# ADAPTER_WOLF.net
KiCad netlist of a schematic drawn in Altium Designer
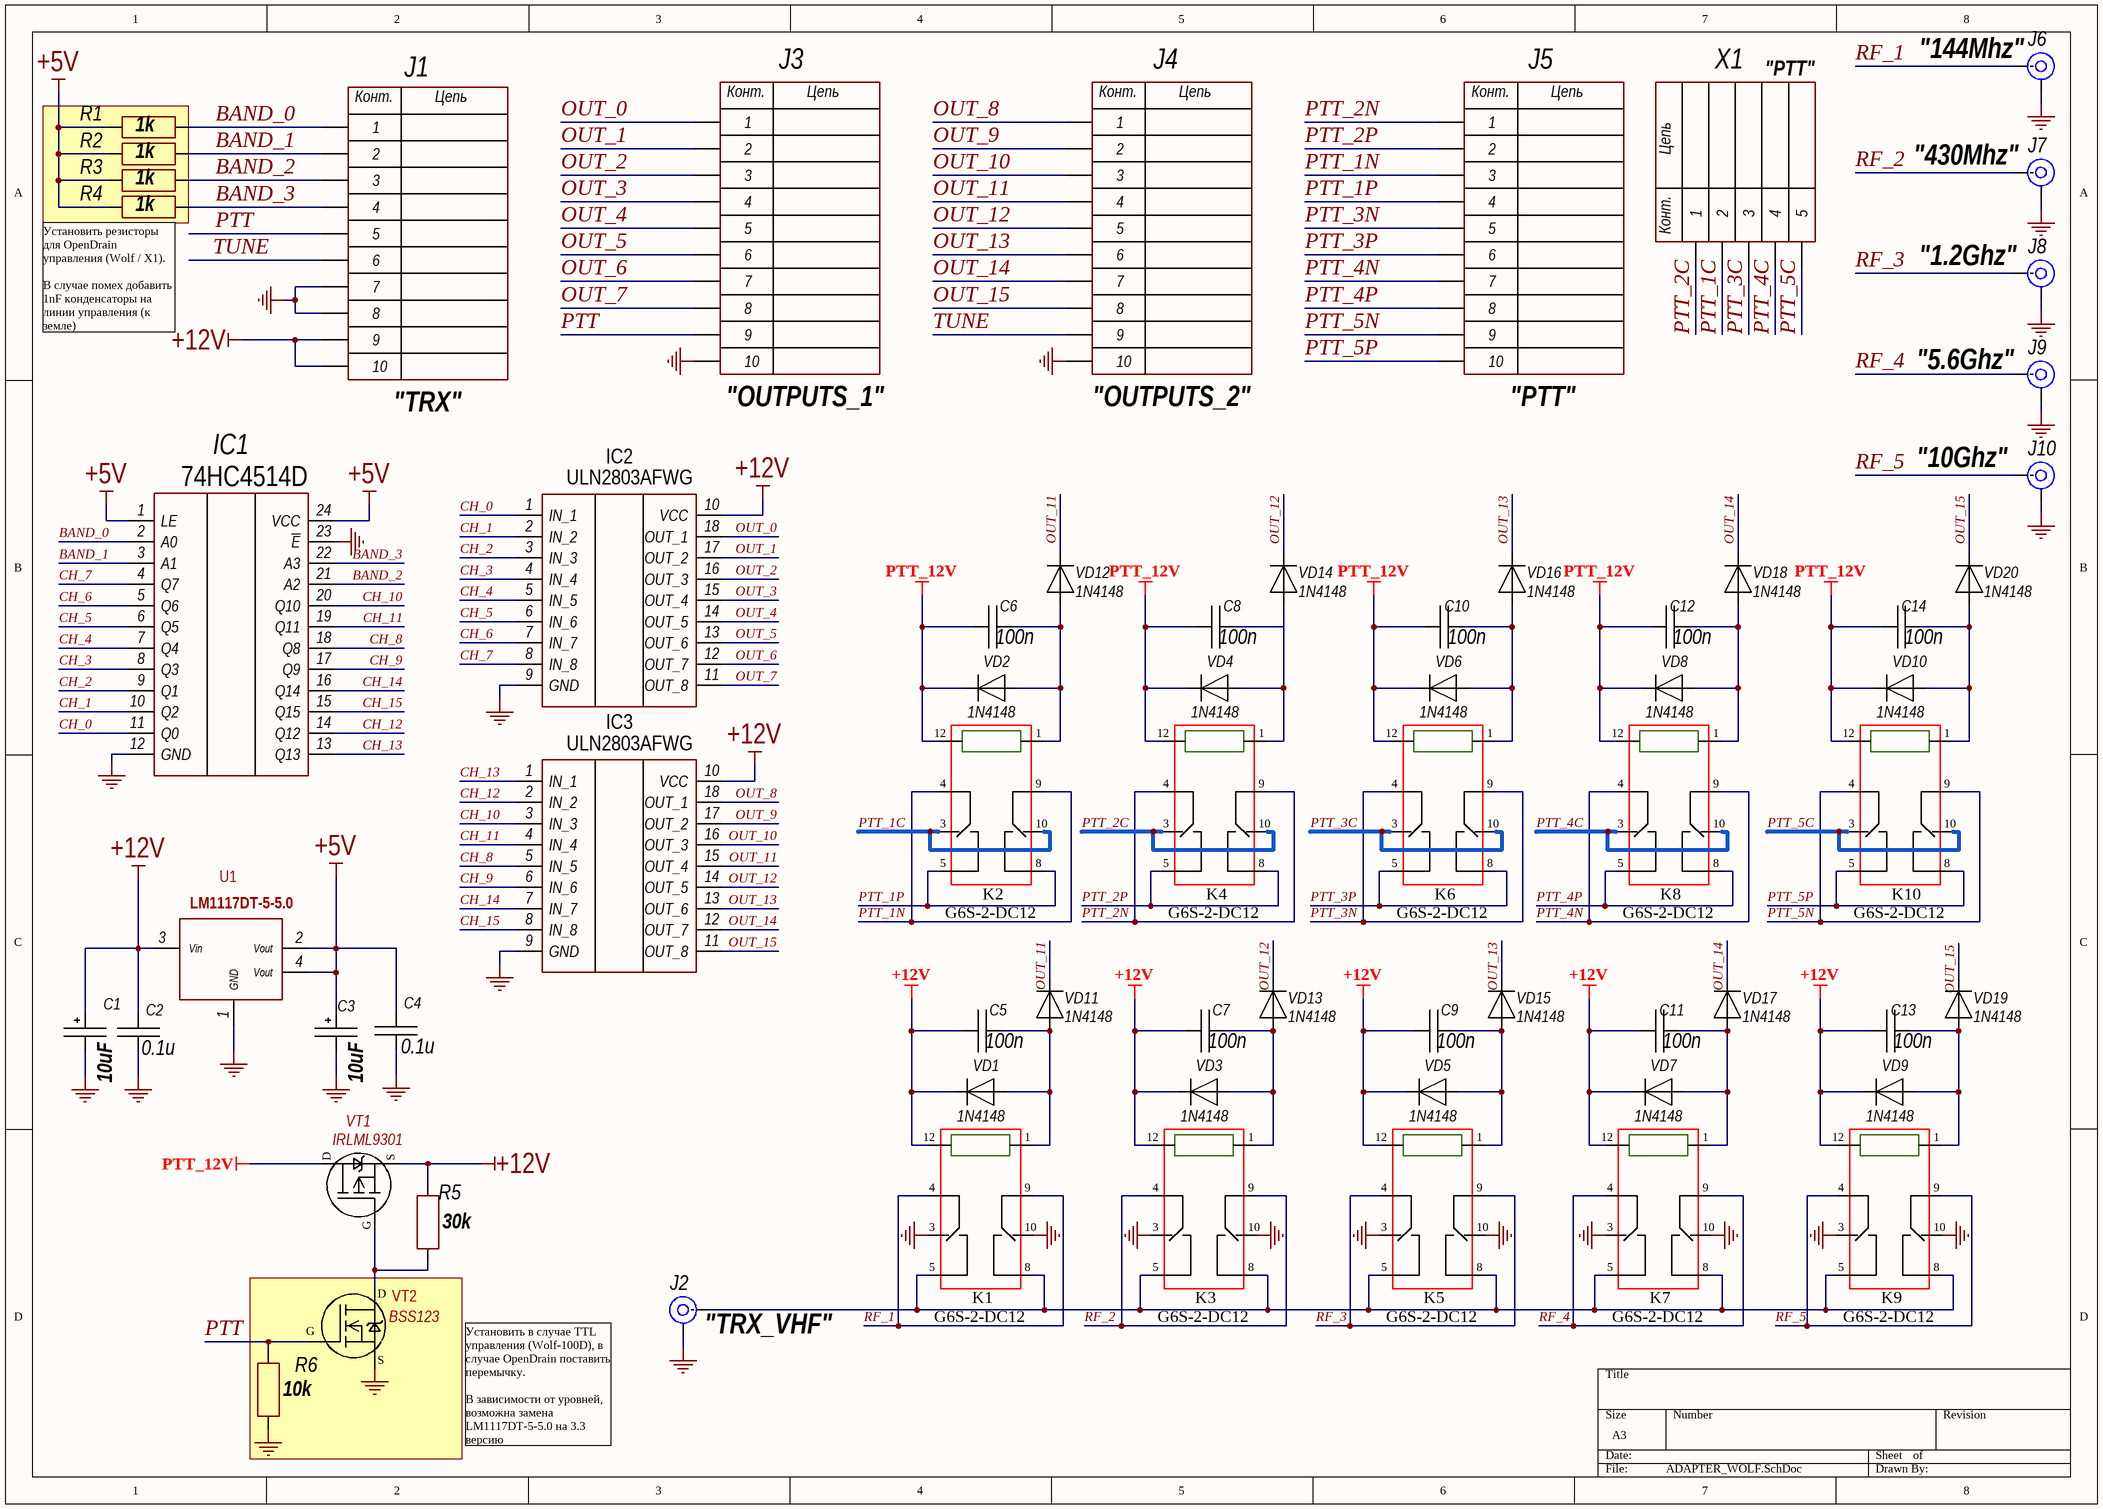
[diagram p0: ADAPTER_WOLF.SchDoc]

(export (version "E")
  (design (tool "Eeschema 10.0.6"))
  (components
    (comp (ref "C1")
      (value "10uF")
      (footprint "standard:TANTAL_B")
      (libsource (lib "Discrete") (part "TantalCap"))
    )
    (comp (ref "C2")
      (value "0.1u")
      (footprint "standard:CH0805C")
      (libsource (lib "Discrete") (part "Capacitor"))
    )
    (comp (ref "C3")
      (value "10uF")
      (footprint "standard:TANTAL_B")
      (libsource (lib "Discrete") (part "TantalCap"))
    )
    (comp (ref "C4")
      (value "0.1u")
      (footprint "standard:CH0805C")
      (libsource (lib "Discrete") (part "Capacitor"))
    )
    (comp (ref "C5")
      (value "100n")
      (footprint "standard:CH0805C")
      (libsource (lib "Discrete") (part "Capacitor"))
    )
    (comp (ref "C6")
      (value "100n")
      (footprint "standard:CH0805C")
      (libsource (lib "Discrete") (part "Capacitor"))
    )
    (comp (ref "C7")
      (value "100n")
      (footprint "standard:CH0805C")
      (libsource (lib "Discrete") (part "Capacitor"))
    )
    (comp (ref "C8")
      (value "100n")
      (footprint "standard:CH0805C")
      (libsource (lib "Discrete") (part "Capacitor"))
    )
    (comp (ref "C9")
      (value "100n")
      (footprint "standard:CH0805C")
      (libsource (lib "Discrete") (part "Capacitor"))
    )
    (comp (ref "C10")
      (value "100n")
      (footprint "standard:CH0805C")
      (libsource (lib "Discrete") (part "Capacitor"))
    )
    (comp (ref "C11")
      (value "100n")
      (footprint "standard:CH0805C")
      (libsource (lib "Discrete") (part "Capacitor"))
    )
    (comp (ref "C12")
      (value "100n")
      (footprint "standard:CH0805C")
      (libsource (lib "Discrete") (part "Capacitor"))
    )
    (comp (ref "C13")
      (value "100n")
      (footprint "standard:CH0805C")
      (libsource (lib "Discrete") (part "Capacitor"))
    )
    (comp (ref "C14")
      (value "100n")
      (footprint "standard:CH0805C")
      (libsource (lib "Discrete") (part "Capacitor"))
    )
    (comp (ref "IC1")
      (value "74HC4514D")
      (footprint "24-SOIC (W)")
      (libsource (lib "Digital") (part "74HC4514D"))
    )
    (comp (ref "IC2")
      (value "ULN2803AFWG")
      (footprint "18-SOIC (W)")
      (libsource (lib "Digital") (part "ULN2803AFWG"))
    )
    (comp (ref "IC3")
      (value "ULN2803AFWG")
      (footprint "18-SOIC (W)")
      (libsource (lib "Digital") (part "ULN2803AFWG"))
    )
    (comp (ref "J1")
      (value "\"TRX\"")
      (footprint "custom:CON: PLD-10")
      (libsource (lib "Connectors") (part "10-Connector"))
    )
    (comp (ref "J2")
      (value "\"TRX_VHF\"")
      (footprint "custom:CON: SMA")
      (description "RF")
      (libsource (lib "Connectors") (part "SMA"))
    )
    (comp (ref "J3")
      (value "\"OUTPUTS_1\"")
      (footprint "custom:CON: PLD-10")
      (libsource (lib "Connectors") (part "10-Connector"))
    )
    (comp (ref "J4")
      (value "\"OUTPUTS_2\"")
      (footprint "custom:CON: PLD-10")
      (libsource (lib "Connectors") (part "10-Connector"))
    )
    (comp (ref "J5")
      (value "\"PTT\"")
      (footprint "custom:CON: PLD-10")
      (libsource (lib "Connectors") (part "10-Connector"))
    )
    (comp (ref "J6")
      (value "\"144Mhz\"")
      (footprint "custom:CON: SMA")
      (description "RF")
      (libsource (lib "Connectors") (part "SMA"))
    )
    (comp (ref "J7")
      (value "\"430Mhz\"")
      (footprint "custom:CON: SMA")
      (description "RF")
      (libsource (lib "Connectors") (part "SMA"))
    )
    (comp (ref "J8")
      (value "\"1.2Ghz\"")
      (footprint "custom:CON: SMA")
      (description "RF")
      (libsource (lib "Connectors") (part "SMA"))
    )
    (comp (ref "J9")
      (value "\"5.6Ghz\"")
      (footprint "custom:CON: SMA")
      (description "RF")
      (libsource (lib "Connectors") (part "SMA"))
    )
    (comp (ref "J10")
      (value "\"10Ghz\"")
      (footprint "custom:CON: SMA")
      (description "RF")
      (libsource (lib "Connectors") (part "SMA"))
    )
    (comp (ref "K1")
      (value "G6S-2-DС12")
      (footprint "G6S-2-DC12")
      (libsource (lib "Relay") (part "G6S-2_TRS"))
    )
    (comp (ref "K2")
      (value "G6S-2-DС12")
      (footprint "G6S-2-DC12")
      (libsource (lib "Relay") (part "G6S-2_TRS"))
    )
    (comp (ref "K3")
      (value "G6S-2-DС12")
      (footprint "G6S-2-DC12")
      (libsource (lib "Relay") (part "G6S-2_TRS"))
    )
    (comp (ref "K4")
      (value "G6S-2-DС12")
      (footprint "G6S-2-DC12")
      (libsource (lib "Relay") (part "G6S-2_TRS"))
    )
    (comp (ref "K5") (value "G6S-2-DС12") (footprint "G6S-2-DC12") (libsource (lib "") (part "G6S-2_TRS_1")))
    (comp (ref "K6") (value "G6S-2-DС12") (footprint "G6S-2-DC12") (libsource (lib "") (part "G6S-2_TRS_2")))
    (comp (ref "K7")
      (value "G6S-2-DС12")
      (footprint "G6S-2-DC12")
      (libsource (lib "Relay") (part "G6S-2_TRS"))
    )
    (comp (ref "K8")
      (value "G6S-2-DС12")
      (footprint "G6S-2-DC12")
      (libsource (lib "Relay") (part "G6S-2_TRS"))
    )
    (comp (ref "K9")
      (value "G6S-2-DС12")
      (footprint "G6S-2-DC12")
      (libsource (lib "Relay") (part "G6S-2_TRS"))
    )
    (comp (ref "K10")
      (value "G6S-2-DС12")
      (footprint "G6S-2-DC12")
      (libsource (lib "Relay") (part "G6S-2_TRS"))
    )
    (comp (ref "R1")
      (value "1k")
      (footprint "standard:CH0805R")
      (libsource (lib "Discrete") (part "Resistor"))
    )
    (comp (ref "R2")
      (value "1k")
      (footprint "standard:CH0805R")
      (libsource (lib "Discrete") (part "Resistor"))
    )
    (comp (ref "R3") (value "1k") (footprint "standard:CH0805R") (libsource (lib "") (part "Resistor_1")))
    (comp (ref "R4")
      (value "1k")
      (footprint "standard:CH0805R")
      (libsource (lib "Discrete") (part "Resistor"))
    )
    (comp (ref "R5") (value "30k") (footprint "standard:CH0805R") (libsource (lib "") (part "Resistor_2")))
    (comp (ref "R6") (value "10k") (footprint "standard:CH0805R") (libsource (lib "") (part "Resistor_2")))
    (comp (ref "U1") (value "LM1117DT-5-5.0") (footprint "SOT223") (libsource (lib "Analog") (part "AMS117")))
    (comp (ref "VD1") (value "1N4148") (footprint "1N4148") (libsource (lib "Diods") (part "Diod")))
    (comp (ref "VD2") (value "1N4148") (footprint "1N4148") (libsource (lib "Diods") (part "Diod")))
    (comp (ref "VD3") (value "1N4148") (footprint "1N4148") (libsource (lib "Diods") (part "Diod")))
    (comp (ref "VD4") (value "1N4148") (footprint "1N4148") (libsource (lib "Diods") (part "Diod")))
    (comp (ref "VD5") (value "1N4148") (footprint "1N4148") (libsource (lib "Diods") (part "Diod")))
    (comp (ref "VD6") (value "1N4148") (footprint "1N4148") (libsource (lib "Diods") (part "Diod")))
    (comp (ref "VD7") (value "1N4148") (footprint "1N4148") (libsource (lib "Diods") (part "Diod")))
    (comp (ref "VD8") (value "1N4148") (footprint "1N4148") (libsource (lib "Diods") (part "Diod")))
    (comp (ref "VD9") (value "1N4148") (footprint "1N4148") (libsource (lib "Diods") (part "Diod")))
    (comp (ref "VD10") (value "1N4148") (footprint "1N4148") (libsource (lib "Diods") (part "Diod")))
    (comp (ref "VD11") (value "1N4148") (footprint "1N4148") (libsource (lib "Diods") (part "Diod")))
    (comp (ref "VD12") (value "1N4148") (footprint "1N4148") (libsource (lib "Diods") (part "Diod")))
    (comp (ref "VD13") (value "1N4148") (footprint "1N4148") (libsource (lib "Diods") (part "Diod")))
    (comp (ref "VD14") (value "1N4148") (footprint "1N4148") (libsource (lib "Diods") (part "Diod")))
    (comp (ref "VD15") (value "1N4148") (footprint "1N4148") (libsource (lib "Diods") (part "Diod")))
    (comp (ref "VD16") (value "1N4148") (footprint "1N4148") (libsource (lib "Diods") (part "Diod")))
    (comp (ref "VD17") (value "1N4148") (footprint "1N4148") (libsource (lib "Diods") (part "Diod")))
    (comp (ref "VD18") (value "1N4148") (footprint "1N4148") (libsource (lib "Diods") (part "Diod")))
    (comp (ref "VD19") (value "1N4148") (footprint "1N4148") (libsource (lib "Diods") (part "Diod")))
    (comp (ref "VD20") (value "1N4148") (footprint "1N4148") (libsource (lib "Diods") (part "Diod")))
    (comp (ref "VT1")
      (value "IRLML9301")
      (footprint "SOT23_132")
      (libsource (lib "Transistor") (part "P-KANAL"))
    )
    (comp (ref "VT2")
      (value "BSS123")
      (footprint "SOT23_132")
      (libsource (lib "Transistor") (part "N-KANAL"))
    )
    (comp (ref "X1")
      (value "\"PTT\"")
      (footprint "custom:CON: PLS-5")
      (libsource (lib "Connectors") (part "5-Connector"))
    )
  )
  (nets
    (net (code "1") (name "+5V") (class "Default")
      (node (ref "C3") (pin "1") (pinfunction "1_1") (pintype "power_in"))
      (node (ref "C4") (pin "2") (pinfunction "2_2") (pintype "power_in"))
      (node (ref "IC1") (pin "1") (pinfunction "LE_1") (pintype "passive"))
      (node (ref "IC1") (pin "24") (pinfunction "VCC_24") (pintype "passive"))
      (node (ref "R1") (pin "1") (pinfunction "1_1") (pintype "passive"))
      (node (ref "R2") (pin "1") (pinfunction "1_1") (pintype "passive"))
      (node (ref "R3") (pin "1") (pinfunction "1_1") (pintype "passive"))
      (node (ref "R4") (pin "1") (pinfunction "1_1") (pintype "passive"))
      (node (ref "U1") (pin "2") (pinfunction "Vout_2") (pintype "passive"))
      (node (ref "U1") (pin "4") (pinfunction "Vout_4") (pintype "passive"))
    )
    (net (code "2") (name "+12V") (class "Default")
      (node (ref "C1") (pin "1") (pinfunction "1_1") (pintype "power_in"))
      (node (ref "C11") (pin "1") (pinfunction "1_1") (pintype "power_in"))
      (node (ref "C13") (pin "1") (pinfunction "1_1") (pintype "power_in"))
      (node (ref "C2") (pin "2") (pinfunction "2_2") (pintype "power_in"))
      (node (ref "C5") (pin "1") (pinfunction "1_1") (pintype "power_in"))
      (node (ref "C7") (pin "1") (pinfunction "1_1") (pintype "power_in"))
      (node (ref "C9") (pin "1") (pinfunction "1_1") (pintype "power_in"))
      (node (ref "IC2") (pin "10") (pinfunction "VCC_10") (pintype "passive"))
      (node (ref "IC3") (pin "10") (pinfunction "VCC_10") (pintype "passive"))
      (node (ref "J1") (pin "10") (pinfunction "10_10") (pintype "power_in"))
      (node (ref "J1") (pin "9") (pinfunction "9_9") (pintype "power_in"))
      (node (ref "K1") (pin "12") (pinfunction "12_12") (pintype "passive"))
      (node (ref "K3") (pin "12") (pinfunction "12_12") (pintype "passive"))
      (node (ref "K5") (pin "12") (pinfunction "2_12") (pintype "passive"))
      (node (ref "K7") (pin "12") (pinfunction "12_12") (pintype "passive"))
      (node (ref "K9") (pin "12") (pinfunction "12_12") (pintype "passive"))
      (node (ref "R5") (pin "2") (pinfunction "2_2") (pintype "passive"))
      (node (ref "U1") (pin "3") (pinfunction "Vin_3") (pintype "passive"))
      (node (ref "VD1") (pin "2") (pinfunction "2_2") (pintype "passive"))
      (node (ref "VD3") (pin "2") (pinfunction "2_2") (pintype "passive"))
      (node (ref "VD5") (pin "2") (pinfunction "2_2") (pintype "passive"))
      (node (ref "VD7") (pin "2") (pinfunction "2_2") (pintype "passive"))
      (node (ref "VD9") (pin "2") (pinfunction "2_2") (pintype "passive"))
      (node (ref "VT1") (pin "2") (pinfunction "Исток_2") (pintype "passive"))
    )
    (net (code "3") (name "/BAND_0") (class "Default")
      (node (ref "IC1") (pin "2") (pinfunction "A0_2") (pintype "passive"))
      (node (ref "J1") (pin "1") (pinfunction "1_1") (pintype "passive"))
      (node (ref "R1") (pin "2") (pinfunction "2_2") (pintype "passive"))
    )
    (net (code "4") (name "/BAND_1") (class "Default")
      (node (ref "IC1") (pin "3") (pinfunction "A1_3") (pintype "passive"))
      (node (ref "J1") (pin "2") (pinfunction "2_2") (pintype "passive"))
      (node (ref "R2") (pin "2") (pinfunction "2_2") (pintype "passive"))
    )
    (net (code "5") (name "/BAND_2") (class "Default")
      (node (ref "IC1") (pin "21") (pinfunction "A2_21") (pintype "passive"))
      (node (ref "J1") (pin "3") (pinfunction "3_3") (pintype "power_in"))
      (node (ref "R3") (pin "2") (pinfunction "2_2") (pintype "passive"))
    )
    (net (code "6") (name "/BAND_3") (class "Default")
      (node (ref "IC1") (pin "22") (pinfunction "A3_22") (pintype "passive"))
      (node (ref "J1") (pin "4") (pinfunction "4_4") (pintype "power_in"))
      (node (ref "R4") (pin "2") (pinfunction "2_2") (pintype "passive"))
    )
    (net (code "7") (name "/CH_0") (class "Default")
      (node (ref "IC1") (pin "11") (pinfunction "Q0_11") (pintype "passive"))
      (node (ref "IC2") (pin "1") (pinfunction "IN_1_1") (pintype "passive"))
    )
    (net (code "8") (name "/CH_1") (class "Default")
      (node (ref "IC1") (pin "10") (pinfunction "Q2_10") (pintype "passive"))
      (node (ref "IC2") (pin "2") (pinfunction "IN_2_2") (pintype "passive"))
    )
    (net (code "9") (name "/CH_2") (class "Default")
      (node (ref "IC1") (pin "9") (pinfunction "Q1_9") (pintype "passive"))
      (node (ref "IC2") (pin "3") (pinfunction "IN_3_3") (pintype "passive"))
    )
    (net (code "10") (name "/CH_3") (class "Default")
      (node (ref "IC1") (pin "8") (pinfunction "Q3_8") (pintype "passive"))
      (node (ref "IC2") (pin "4") (pinfunction "IN_4_4") (pintype "passive"))
    )
    (net (code "11") (name "/CH_4") (class "Default")
      (node (ref "IC1") (pin "7") (pinfunction "Q4_7") (pintype "passive"))
      (node (ref "IC2") (pin "5") (pinfunction "IN_5_5") (pintype "passive"))
    )
    (net (code "12") (name "/CH_5") (class "Default")
      (node (ref "IC1") (pin "6") (pinfunction "Q5_6") (pintype "passive"))
      (node (ref "IC2") (pin "6") (pinfunction "IN_6_6") (pintype "passive"))
    )
    (net (code "13") (name "/CH_6") (class "Default")
      (node (ref "IC1") (pin "5") (pinfunction "Q6_5") (pintype "passive"))
      (node (ref "IC2") (pin "7") (pinfunction "IN_7_7") (pintype "passive"))
    )
    (net (code "14") (name "/CH_7") (class "Default")
      (node (ref "IC1") (pin "4") (pinfunction "Q7_4") (pintype "passive"))
      (node (ref "IC2") (pin "8") (pinfunction "IN_8_8") (pintype "passive"))
    )
    (net (code "15") (name "/CH_8") (class "Default")
      (node (ref "IC1") (pin "18") (pinfunction "Q8_18") (pintype "passive"))
      (node (ref "IC3") (pin "5") (pinfunction "IN_5_5") (pintype "passive"))
    )
    (net (code "16") (name "/CH_9") (class "Default")
      (node (ref "IC1") (pin "17") (pinfunction "Q9_17") (pintype "passive"))
      (node (ref "IC3") (pin "6") (pinfunction "IN_6_6") (pintype "passive"))
    )
    (net (code "17") (name "/CH_10") (class "Default")
      (node (ref "IC1") (pin "20") (pinfunction "Q10_20") (pintype "passive"))
      (node (ref "IC3") (pin "3") (pinfunction "IN_3_3") (pintype "passive"))
    )
    (net (code "18") (name "/CH_11") (class "Default")
      (node (ref "IC1") (pin "19") (pinfunction "Q11_19") (pintype "passive"))
      (node (ref "IC3") (pin "4") (pinfunction "IN_4_4") (pintype "passive"))
    )
    (net (code "19") (name "/CH_12") (class "Default")
      (node (ref "IC1") (pin "14") (pinfunction "Q12_14") (pintype "passive"))
      (node (ref "IC3") (pin "2") (pinfunction "IN_2_2") (pintype "passive"))
    )
    (net (code "20") (name "/CH_13") (class "Default")
      (node (ref "IC1") (pin "13") (pinfunction "Q13_13") (pintype "passive"))
      (node (ref "IC3") (pin "1") (pinfunction "IN_1_1") (pintype "passive"))
    )
    (net (code "21") (name "/CH_14") (class "Default")
      (node (ref "IC1") (pin "16") (pinfunction "Q14_16") (pintype "passive"))
      (node (ref "IC3") (pin "7") (pinfunction "IN_7_7") (pintype "passive"))
    )
    (net (code "22") (name "/CH_15") (class "Default")
      (node (ref "IC1") (pin "15") (pinfunction "Q15_15") (pintype "passive"))
      (node (ref "IC3") (pin "8") (pinfunction "IN_8_8") (pintype "passive"))
    )
    (net (code "23") (name "/OUT_0") (class "Default")
      (node (ref "IC2") (pin "18") (pinfunction "OUT_1_18") (pintype "passive"))
      (node (ref "J3") (pin "1") (pinfunction "1_1") (pintype "passive"))
    )
    (net (code "24") (name "/OUT_1") (class "Default")
      (node (ref "IC2") (pin "17") (pinfunction "OUT_2_17") (pintype "passive"))
      (node (ref "J3") (pin "2") (pinfunction "2_2") (pintype "passive"))
    )
    (net (code "25") (name "/OUT_2") (class "Default")
      (node (ref "IC2") (pin "16") (pinfunction "OUT_3_16") (pintype "passive"))
      (node (ref "J3") (pin "3") (pinfunction "3_3") (pintype "power_in"))
    )
    (net (code "26") (name "/OUT_3") (class "Default")
      (node (ref "IC2") (pin "15") (pinfunction "OUT_4_15") (pintype "passive"))
      (node (ref "J3") (pin "4") (pinfunction "4_4") (pintype "power_in"))
    )
    (net (code "27") (name "/OUT_4") (class "Default")
      (node (ref "IC2") (pin "14") (pinfunction "OUT_5_14") (pintype "passive"))
      (node (ref "J3") (pin "5") (pinfunction "5_5") (pintype "power_in"))
    )
    (net (code "28") (name "/OUT_5") (class "Default")
      (node (ref "IC2") (pin "13") (pinfunction "OUT_6_13") (pintype "passive"))
      (node (ref "J3") (pin "6") (pinfunction "6_6") (pintype "power_in"))
    )
    (net (code "29") (name "/OUT_6") (class "Default")
      (node (ref "IC2") (pin "12") (pinfunction "OUT_7_12") (pintype "passive"))
      (node (ref "J3") (pin "7") (pinfunction "7_7") (pintype "power_in"))
    )
    (net (code "30") (name "/OUT_7") (class "Default")
      (node (ref "IC2") (pin "11") (pinfunction "OUT_8_11") (pintype "passive"))
      (node (ref "J3") (pin "8") (pinfunction "8_8") (pintype "power_in"))
    )
    (net (code "31") (name "/OUT_8") (class "Default")
      (node (ref "IC3") (pin "18") (pinfunction "OUT_1_18") (pintype "passive"))
      (node (ref "J4") (pin "1") (pinfunction "1_1") (pintype "passive"))
    )
    (net (code "32") (name "/OUT_9") (class "Default")
      (node (ref "IC3") (pin "17") (pinfunction "OUT_2_17") (pintype "passive"))
      (node (ref "J4") (pin "2") (pinfunction "2_2") (pintype "passive"))
    )
    (net (code "33") (name "/OUT_10") (class "Default")
      (node (ref "IC3") (pin "16") (pinfunction "OUT_3_16") (pintype "passive"))
      (node (ref "J4") (pin "3") (pinfunction "3_3") (pintype "power_in"))
    )
    (net (code "34") (name "/OUT_11") (class "Default")
      (node (ref "IC3") (pin "15") (pinfunction "OUT_4_15") (pintype "passive"))
      (node (ref "J4") (pin "4") (pinfunction "4_4") (pintype "power_in"))
      (node (ref "VD11") (pin "2") (pinfunction "2_2") (pintype "passive"))
      (node (ref "VD12") (pin "2") (pinfunction "2_2") (pintype "passive"))
    )
    (net (code "35") (name "/OUT_12") (class "Default")
      (node (ref "IC3") (pin "14") (pinfunction "OUT_5_14") (pintype "passive"))
      (node (ref "J4") (pin "5") (pinfunction "5_5") (pintype "power_in"))
      (node (ref "VD13") (pin "2") (pinfunction "2_2") (pintype "passive"))
      (node (ref "VD14") (pin "2") (pinfunction "2_2") (pintype "passive"))
    )
    (net (code "36") (name "/OUT_13") (class "Default")
      (node (ref "IC3") (pin "13") (pinfunction "OUT_6_13") (pintype "passive"))
      (node (ref "J4") (pin "6") (pinfunction "6_6") (pintype "power_in"))
      (node (ref "VD15") (pin "2") (pinfunction "2_2") (pintype "passive"))
      (node (ref "VD16") (pin "2") (pinfunction "2_2") (pintype "passive"))
    )
    (net (code "37") (name "/OUT_14") (class "Default")
      (node (ref "IC3") (pin "12") (pinfunction "OUT_7_12") (pintype "passive"))
      (node (ref "J4") (pin "7") (pinfunction "7_7") (pintype "power_in"))
      (node (ref "VD17") (pin "2") (pinfunction "2_2") (pintype "passive"))
      (node (ref "VD18") (pin "2") (pinfunction "2_2") (pintype "passive"))
    )
    (net (code "38") (name "/OUT_15") (class "Default")
      (node (ref "IC3") (pin "11") (pinfunction "OUT_8_11") (pintype "passive"))
      (node (ref "J4") (pin "8") (pinfunction "8_8") (pintype "power_in"))
      (node (ref "VD19") (pin "2") (pinfunction "2_2") (pintype "passive"))
      (node (ref "VD20") (pin "2") (pinfunction "2_2") (pintype "passive"))
    )
    (net (code "39") (name "/PTT") (class "Default")
      (node (ref "J1") (pin "5") (pinfunction "5_5") (pintype "power_in"))
      (node (ref "J3") (pin "9") (pinfunction "9_9") (pintype "power_in"))
      (node (ref "R6") (pin "2") (pinfunction "2_2") (pintype "passive"))
      (node (ref "VT2") (pin "1") (pinfunction "Затвор_1") (pintype "passive"))
    )
    (net (code "40") (name "/PTT_1N") (class "Default")
      (node (ref "J5") (pin "3") (pinfunction "3_3") (pintype "power_in"))
      (node (ref "K2") (pin "4") (pinfunction "4_4") (pintype "passive"))
      (node (ref "K2") (pin "9") (pinfunction "9_9") (pintype "passive"))
    )
    (net (code "41") (name "/PTT_1P") (class "Default")
      (node (ref "J5") (pin "4") (pinfunction "4_4") (pintype "power_in"))
      (node (ref "K2") (pin "5") (pinfunction "5_5") (pintype "passive"))
      (node (ref "K2") (pin "8") (pinfunction "8_8") (pintype "passive"))
    )
    (net (code "42") (name "/PTT_1С") (class "Default")
      (node (ref "K2") (pin "10") (pinfunction "10_10") (pintype "passive"))
      (node (ref "K2") (pin "3") (pinfunction "3_3") (pintype "passive"))
      (node (ref "X1") (pin "2") (pinfunction "2_2") (pintype "passive"))
    )
    (net (code "43") (name "/PTT_2N") (class "Default")
      (node (ref "J5") (pin "1") (pinfunction "1_1") (pintype "passive"))
      (node (ref "K4") (pin "4") (pinfunction "4_4") (pintype "passive"))
      (node (ref "K4") (pin "9") (pinfunction "9_9") (pintype "passive"))
    )
    (net (code "44") (name "/PTT_2P") (class "Default")
      (node (ref "J5") (pin "2") (pinfunction "2_2") (pintype "passive"))
      (node (ref "K4") (pin "5") (pinfunction "5_5") (pintype "passive"))
      (node (ref "K4") (pin "8") (pinfunction "8_8") (pintype "passive"))
    )
    (net (code "45") (name "/PTT_2С") (class "Default")
      (node (ref "K4") (pin "10") (pinfunction "10_10") (pintype "passive"))
      (node (ref "K4") (pin "3") (pinfunction "3_3") (pintype "passive"))
      (node (ref "X1") (pin "1") (pinfunction "1_1") (pintype "passive"))
    )
    (net (code "46") (name "/PTT_3N") (class "Default")
      (node (ref "J5") (pin "5") (pinfunction "5_5") (pintype "power_in"))
      (node (ref "K6") (pin "4") (pinfunction "4_4") (pintype "passive"))
      (node (ref "K6") (pin "9") (pinfunction "9_9") (pintype "passive"))
    )
    (net (code "47") (name "/PTT_3P") (class "Default")
      (node (ref "J5") (pin "6") (pinfunction "6_6") (pintype "power_in"))
      (node (ref "K6") (pin "5") (pinfunction "5_5") (pintype "passive"))
      (node (ref "K6") (pin "8") (pinfunction "8_8") (pintype "passive"))
    )
    (net (code "48") (name "/PTT_3С") (class "Default")
      (node (ref "K6") (pin "10") (pinfunction "10_10") (pintype "passive"))
      (node (ref "K6") (pin "3") (pinfunction "3_3") (pintype "passive"))
      (node (ref "X1") (pin "3") (pinfunction "3_3") (pintype "power_in"))
    )
    (net (code "49") (name "/PTT_4N") (class "Default")
      (node (ref "J5") (pin "7") (pinfunction "7_7") (pintype "power_in"))
      (node (ref "K8") (pin "4") (pinfunction "4_4") (pintype "passive"))
      (node (ref "K8") (pin "9") (pinfunction "9_9") (pintype "passive"))
    )
    (net (code "50") (name "/PTT_4P") (class "Default")
      (node (ref "J5") (pin "8") (pinfunction "8_8") (pintype "power_in"))
      (node (ref "K8") (pin "5") (pinfunction "5_5") (pintype "passive"))
      (node (ref "K8") (pin "8") (pinfunction "8_8") (pintype "passive"))
    )
    (net (code "51") (name "/PTT_4С") (class "Default")
      (node (ref "K8") (pin "10") (pinfunction "10_10") (pintype "passive"))
      (node (ref "K8") (pin "3") (pinfunction "3_3") (pintype "passive"))
      (node (ref "X1") (pin "4") (pinfunction "4_4") (pintype "power_in"))
    )
    (net (code "52") (name "/PTT_5N") (class "Default")
      (node (ref "J5") (pin "9") (pinfunction "9_9") (pintype "power_in"))
      (node (ref "K10") (pin "4") (pinfunction "4_4") (pintype "passive"))
      (node (ref "K10") (pin "9") (pinfunction "9_9") (pintype "passive"))
    )
    (net (code "53") (name "/PTT_5P") (class "Default")
      (node (ref "J5") (pin "10") (pinfunction "10_10") (pintype "power_in"))
      (node (ref "K10") (pin "5") (pinfunction "5_5") (pintype "passive"))
      (node (ref "K10") (pin "8") (pinfunction "8_8") (pintype "passive"))
    )
    (net (code "54") (name "/PTT_5С") (class "Default")
      (node (ref "K10") (pin "10") (pinfunction "10_10") (pintype "passive"))
      (node (ref "K10") (pin "3") (pinfunction "3_3") (pintype "passive"))
      (node (ref "X1") (pin "5") (pinfunction "5_5") (pintype "power_in"))
    )
    (net (code "55") (name "/RF_1") (class "Default")
      (node (ref "J6") (pin "1") (pinfunction "IN_1") (pintype "passive"))
      (node (ref "K1") (pin "4") (pinfunction "4_4") (pintype "passive"))
      (node (ref "K1") (pin "9") (pinfunction "9_9") (pintype "passive"))
    )
    (net (code "56") (name "/RF_2") (class "Default")
      (node (ref "J7") (pin "1") (pinfunction "IN_1") (pintype "passive"))
      (node (ref "K3") (pin "4") (pinfunction "4_4") (pintype "passive"))
      (node (ref "K3") (pin "9") (pinfunction "9_9") (pintype "passive"))
    )
    (net (code "57") (name "/RF_3") (class "Default")
      (node (ref "J8") (pin "1") (pinfunction "IN_1") (pintype "passive"))
      (node (ref "K5") (pin "4") (pinfunction "4_4") (pintype "passive"))
      (node (ref "K5") (pin "9") (pinfunction "9_9") (pintype "passive"))
    )
    (net (code "58") (name "/RF_4") (class "Default")
      (node (ref "J9") (pin "1") (pinfunction "IN_1") (pintype "passive"))
      (node (ref "K7") (pin "4") (pinfunction "4_4") (pintype "passive"))
      (node (ref "K7") (pin "9") (pinfunction "9_9") (pintype "passive"))
    )
    (net (code "59") (name "/RF_5") (class "Default")
      (node (ref "J10") (pin "1") (pinfunction "IN_1") (pintype "passive"))
      (node (ref "K9") (pin "4") (pinfunction "4_4") (pintype "passive"))
      (node (ref "K9") (pin "9") (pinfunction "9_9") (pintype "passive"))
    )
    (net (code "60") (name "/TUNE") (class "Default")
      (node (ref "J1") (pin "6") (pinfunction "6_6") (pintype "power_in"))
      (node (ref "J4") (pin "9") (pinfunction "9_9") (pintype "power_in"))
    )
    (net (code "61") (name "GND") (class "Default")
      (node (ref "C1") (pin "2") (pinfunction "2_2") (pintype "power_in"))
      (node (ref "C2") (pin "1") (pinfunction "1_1") (pintype "power_in"))
      (node (ref "C3") (pin "2") (pinfunction "2_2") (pintype "power_in"))
      (node (ref "C4") (pin "1") (pinfunction "1_1") (pintype "power_in"))
      (node (ref "IC1") (pin "12") (pinfunction "GND_12") (pintype "passive"))
      (node (ref "IC1") (pin "23") (pinfunction "~{E}_23") (pintype "passive"))
      (node (ref "IC2") (pin "9") (pinfunction "GND_9") (pintype "passive"))
      (node (ref "IC3") (pin "9") (pinfunction "GND_9") (pintype "passive"))
      (node (ref "J1") (pin "7") (pinfunction "7_7") (pintype "power_in"))
      (node (ref "J1") (pin "8") (pinfunction "8_8") (pintype "power_in"))
      (node (ref "J10") (pin "2") (pinfunction "IN_2") (pintype "passive"))
      (node (ref "J2") (pin "2") (pinfunction "IN_2") (pintype "passive"))
      (node (ref "J3") (pin "10") (pinfunction "10_10") (pintype "power_in"))
      (node (ref "J4") (pin "10") (pinfunction "10_10") (pintype "power_in"))
      (node (ref "J6") (pin "2") (pinfunction "IN_2") (pintype "passive"))
      (node (ref "J7") (pin "2") (pinfunction "IN_2") (pintype "passive"))
      (node (ref "J8") (pin "2") (pinfunction "IN_2") (pintype "passive"))
      (node (ref "J9") (pin "2") (pinfunction "IN_2") (pintype "passive"))
      (node (ref "K1") (pin "10") (pinfunction "10_10") (pintype "passive"))
      (node (ref "K1") (pin "3") (pinfunction "3_3") (pintype "passive"))
      (node (ref "K3") (pin "10") (pinfunction "10_10") (pintype "passive"))
      (node (ref "K3") (pin "3") (pinfunction "3_3") (pintype "passive"))
      (node (ref "K5") (pin "10") (pinfunction "10_10") (pintype "passive"))
      (node (ref "K5") (pin "3") (pinfunction "3_3") (pintype "passive"))
      (node (ref "K7") (pin "10") (pinfunction "10_10") (pintype "passive"))
      (node (ref "K7") (pin "3") (pinfunction "3_3") (pintype "passive"))
      (node (ref "K9") (pin "10") (pinfunction "10_10") (pintype "passive"))
      (node (ref "K9") (pin "3") (pinfunction "3_3") (pintype "passive"))
      (node (ref "R6") (pin "1") (pinfunction "1_1") (pintype "passive"))
      (node (ref "U1") (pin "1") (pinfunction "GND_1") (pintype "passive"))
      (node (ref "VT2") (pin "2") (pinfunction "Исток_2") (pintype "passive"))
    )
    (net (code "62") (name "Net-(C5-Pad2)") (class "Default")
      (node (ref "C5") (pin "2") (pinfunction "2_2") (pintype "power_in"))
      (node (ref "K1") (pin "1") (pinfunction "1_1") (pintype "passive"))
      (node (ref "VD1") (pin "1") (pinfunction "1_1") (pintype "passive"))
      (node (ref "VD11") (pin "1") (pinfunction "1_1") (pintype "passive"))
    )
    (net (code "63") (name "Net-(C6-Pad2)") (class "Default")
      (node (ref "C6") (pin "2") (pinfunction "2_2") (pintype "power_in"))
      (node (ref "K2") (pin "1") (pinfunction "1_1") (pintype "passive"))
      (node (ref "VD12") (pin "1") (pinfunction "1_1") (pintype "passive"))
      (node (ref "VD2") (pin "1") (pinfunction "1_1") (pintype "passive"))
    )
    (net (code "64") (name "Net-(C7-Pad2)") (class "Default")
      (node (ref "C7") (pin "2") (pinfunction "2_2") (pintype "power_in"))
      (node (ref "K3") (pin "1") (pinfunction "1_1") (pintype "passive"))
      (node (ref "VD13") (pin "1") (pinfunction "1_1") (pintype "passive"))
      (node (ref "VD3") (pin "1") (pinfunction "1_1") (pintype "passive"))
    )
    (net (code "65") (name "Net-(C8-Pad2)") (class "Default")
      (node (ref "C8") (pin "2") (pinfunction "2_2") (pintype "power_in"))
      (node (ref "K4") (pin "1") (pinfunction "1_1") (pintype "passive"))
      (node (ref "VD14") (pin "1") (pinfunction "1_1") (pintype "passive"))
      (node (ref "VD4") (pin "1") (pinfunction "1_1") (pintype "passive"))
    )
    (net (code "66") (name "Net-(C9-Pad2)") (class "Default")
      (node (ref "C9") (pin "2") (pinfunction "2_2") (pintype "power_in"))
      (node (ref "K5") (pin "1") (pinfunction "1_1") (pintype "passive"))
      (node (ref "VD15") (pin "1") (pinfunction "1_1") (pintype "passive"))
      (node (ref "VD5") (pin "1") (pinfunction "1_1") (pintype "passive"))
    )
    (net (code "67") (name "Net-(C10-Pad2)") (class "Default")
      (node (ref "C10") (pin "2") (pinfunction "2_2") (pintype "power_in"))
      (node (ref "K6") (pin "1") (pinfunction "1_1") (pintype "passive"))
      (node (ref "VD16") (pin "1") (pinfunction "1_1") (pintype "passive"))
      (node (ref "VD6") (pin "1") (pinfunction "1_1") (pintype "passive"))
    )
    (net (code "68") (name "Net-(C11-Pad2)") (class "Default")
      (node (ref "C11") (pin "2") (pinfunction "2_2") (pintype "power_in"))
      (node (ref "K7") (pin "1") (pinfunction "1_1") (pintype "passive"))
      (node (ref "VD17") (pin "1") (pinfunction "1_1") (pintype "passive"))
      (node (ref "VD7") (pin "1") (pinfunction "1_1") (pintype "passive"))
    )
    (net (code "69") (name "Net-(C12-Pad2)") (class "Default")
      (node (ref "C12") (pin "2") (pinfunction "2_2") (pintype "power_in"))
      (node (ref "K8") (pin "1") (pinfunction "1_1") (pintype "passive"))
      (node (ref "VD18") (pin "1") (pinfunction "1_1") (pintype "passive"))
      (node (ref "VD8") (pin "1") (pinfunction "1_1") (pintype "passive"))
    )
    (net (code "70") (name "Net-(C13-Pad2)") (class "Default")
      (node (ref "C13") (pin "2") (pinfunction "2_2") (pintype "power_in"))
      (node (ref "K9") (pin "1") (pinfunction "1_1") (pintype "passive"))
      (node (ref "VD19") (pin "1") (pinfunction "1_1") (pintype "passive"))
      (node (ref "VD9") (pin "1") (pinfunction "1_1") (pintype "passive"))
    )
    (net (code "71") (name "Net-(C14-Pad2)") (class "Default")
      (node (ref "C14") (pin "2") (pinfunction "2_2") (pintype "power_in"))
      (node (ref "K10") (pin "1") (pinfunction "1_1") (pintype "passive"))
      (node (ref "VD10") (pin "1") (pinfunction "1_1") (pintype "passive"))
      (node (ref "VD20") (pin "1") (pinfunction "1_1") (pintype "passive"))
    )
    (net (code "72") (name "Net-(J2-IN-Pad1)") (class "Default")
      (node (ref "J2") (pin "1") (pinfunction "IN_1") (pintype "passive"))
      (node (ref "K1") (pin "5") (pinfunction "5_5") (pintype "passive"))
      (node (ref "K1") (pin "8") (pinfunction "8_8") (pintype "passive"))
      (node (ref "K3") (pin "5") (pinfunction "5_5") (pintype "passive"))
      (node (ref "K3") (pin "8") (pinfunction "8_8") (pintype "passive"))
      (node (ref "K5") (pin "5") (pinfunction "5_5") (pintype "passive"))
      (node (ref "K5") (pin "8") (pinfunction "8_8") (pintype "passive"))
      (node (ref "K7") (pin "5") (pinfunction "5_5") (pintype "passive"))
      (node (ref "K7") (pin "8") (pinfunction "8_8") (pintype "passive"))
      (node (ref "K9") (pin "5") (pinfunction "5_5") (pintype "passive"))
      (node (ref "K9") (pin "8") (pinfunction "8_8") (pintype "passive"))
    )
    (net (code "73") (name "Net-(VT1-Затвор(Gate))") (class "Default")
      (node (ref "R5") (pin "1") (pinfunction "1_1") (pintype "passive"))
      (node (ref "VT1") (pin "1") (pinfunction "Затвор(Gate)_1") (pintype "passive"))
      (node (ref "VT2") (pin "3") (pinfunction "Сток_3") (pintype "passive"))
    )
    (net (code "74") (name "PTT_12V") (class "Default")
      (node (ref "C10") (pin "1") (pinfunction "1_1") (pintype "power_in"))
      (node (ref "C12") (pin "1") (pinfunction "1_1") (pintype "power_in"))
      (node (ref "C14") (pin "1") (pinfunction "1_1") (pintype "power_in"))
      (node (ref "C6") (pin "1") (pinfunction "1_1") (pintype "power_in"))
      (node (ref "C8") (pin "1") (pinfunction "1_1") (pintype "power_in"))
      (node (ref "K10") (pin "12") (pinfunction "12_12") (pintype "passive"))
      (node (ref "K2") (pin "12") (pinfunction "12_12") (pintype "passive"))
      (node (ref "K4") (pin "12") (pinfunction "12_12") (pintype "passive"))
      (node (ref "K6") (pin "12") (pinfunction "12_12") (pintype "passive"))
      (node (ref "K8") (pin "12") (pinfunction "12_12") (pintype "passive"))
      (node (ref "VD10") (pin "2") (pinfunction "2_2") (pintype "passive"))
      (node (ref "VD2") (pin "2") (pinfunction "2_2") (pintype "passive"))
      (node (ref "VD4") (pin "2") (pinfunction "2_2") (pintype "passive"))
      (node (ref "VD6") (pin "2") (pinfunction "2_2") (pintype "passive"))
      (node (ref "VD8") (pin "2") (pinfunction "2_2") (pintype "passive"))
      (node (ref "VT1") (pin "3") (pinfunction "Сток_3") (pintype "passive"))
    )
  )
)
